# sensors_b.net
KiCad netlist of a schematic drawn in EAGLE
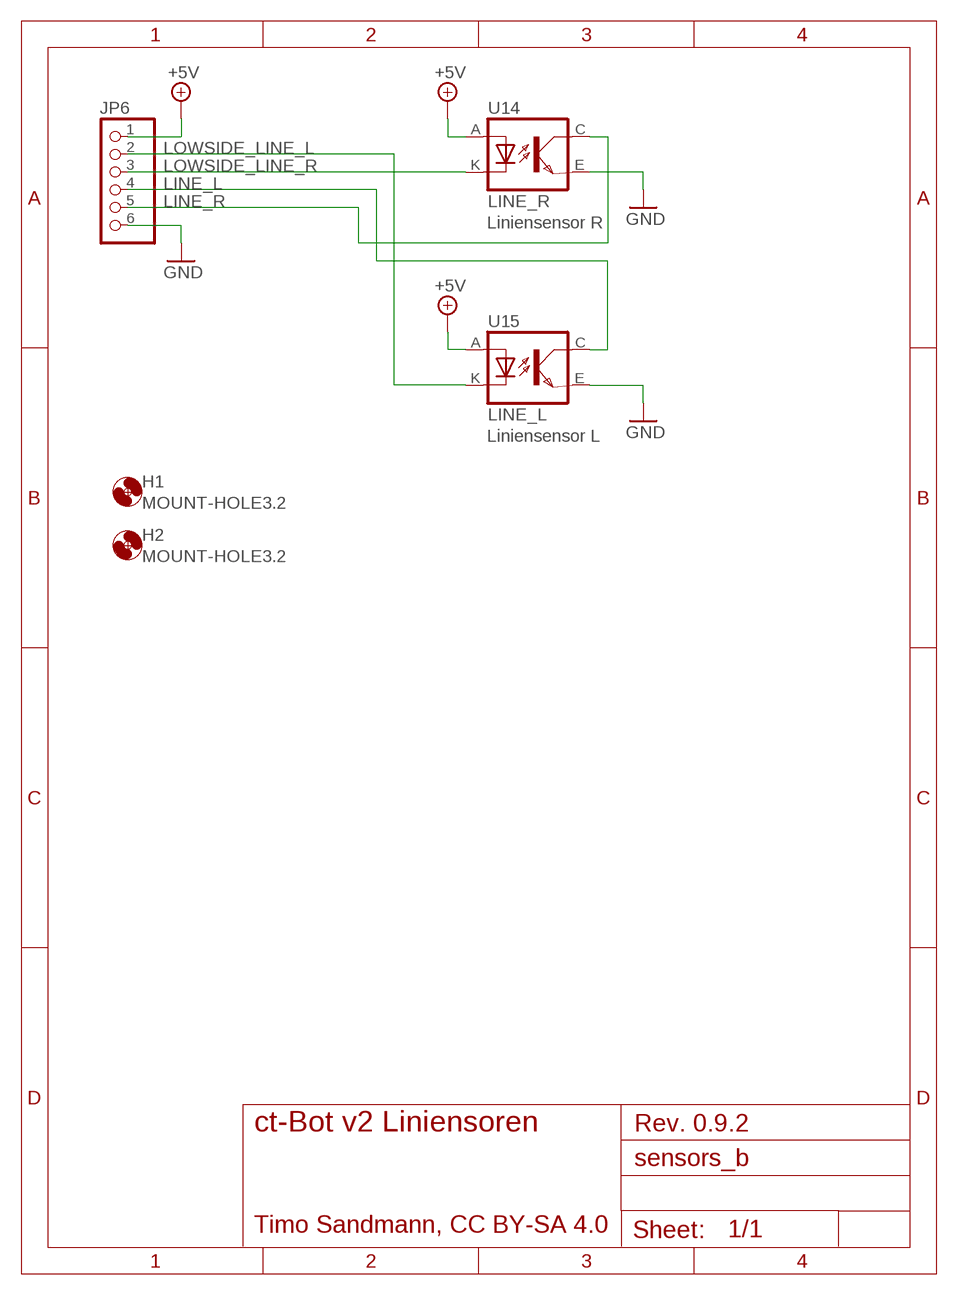
[diagram p0: schematic, sheet 1]

(export (version "E")
  (design (tool "Eeschema 10.0.6"))
  (components
    (comp (ref "H1")
      (value "MOUNT-HOLE3.2")
      (footprint "eagle-import:3,2")
      (libsource (lib "eagle-import") (part "MOUNT-HOLE3.2"))
    )
    (comp (ref "H2")
      (value "MOUNT-HOLE3.2")
      (footprint "eagle-import:3,2")
      (libsource (lib "eagle-import") (part "MOUNT-HOLE3.2"))
    )
    (comp (ref "JP6")
      (value "PINHD-1X6")
      (footprint "eagle-import:1X06")
      (libsource (lib "eagle-import") (part "PINHD-1X6"))
    )
    (comp (ref "U14")
      (value "LINE_R")
      (footprint "eagle-import:4")
      (libsource (lib "eagle-import") (part "CNY70DEF"))
    )
    (comp (ref "U15")
      (value "LINE_L")
      (footprint "eagle-import:4")
      (libsource (lib "eagle-import") (part "CNY70DEF"))
    )
  )
  (nets
    (net (code "1") (name "+5V") (class "Default")
      (node (ref "JP6") (pin "1") (pinfunction "1_1") (pintype "passive"))
      (node (ref "U14") (pin "A") (pinfunction "A_A") (pintype "passive"))
      (node (ref "U15") (pin "A") (pinfunction "A_A") (pintype "passive"))
    )
    (net (code "2") (name "/LINE_L") (class "Default")
      (node (ref "JP6") (pin "4") (pinfunction "4_4") (pintype "passive"))
      (node (ref "U15") (pin "C") (pinfunction "COL_C") (pintype "passive"))
    )
    (net (code "3") (name "/LINE_R") (class "Default")
      (node (ref "JP6") (pin "5") (pinfunction "5_5") (pintype "passive"))
      (node (ref "U14") (pin "C") (pinfunction "COL_C") (pintype "passive"))
    )
    (net (code "4") (name "/LOWSIDE_LINE_L") (class "Default")
      (node (ref "JP6") (pin "2") (pinfunction "2_2") (pintype "passive"))
      (node (ref "U15") (pin "K") (pinfunction "C_K") (pintype "passive"))
    )
    (net (code "5") (name "/LOWSIDE_LINE_R") (class "Default")
      (node (ref "JP6") (pin "3") (pinfunction "3_3") (pintype "passive"))
      (node (ref "U14") (pin "K") (pinfunction "C_K") (pintype "passive"))
    )
    (net (code "6") (name "GND") (class "Default")
      (node (ref "JP6") (pin "6") (pinfunction "6_6") (pintype "passive"))
      (node (ref "U14") (pin "E") (pinfunction "EMI_E") (pintype "passive"))
      (node (ref "U15") (pin "E") (pinfunction "EMI_E") (pintype "passive"))
    )
  )
)
